# ubiquitel.net
KiCad netlist of a schematic drawn in EAGLE
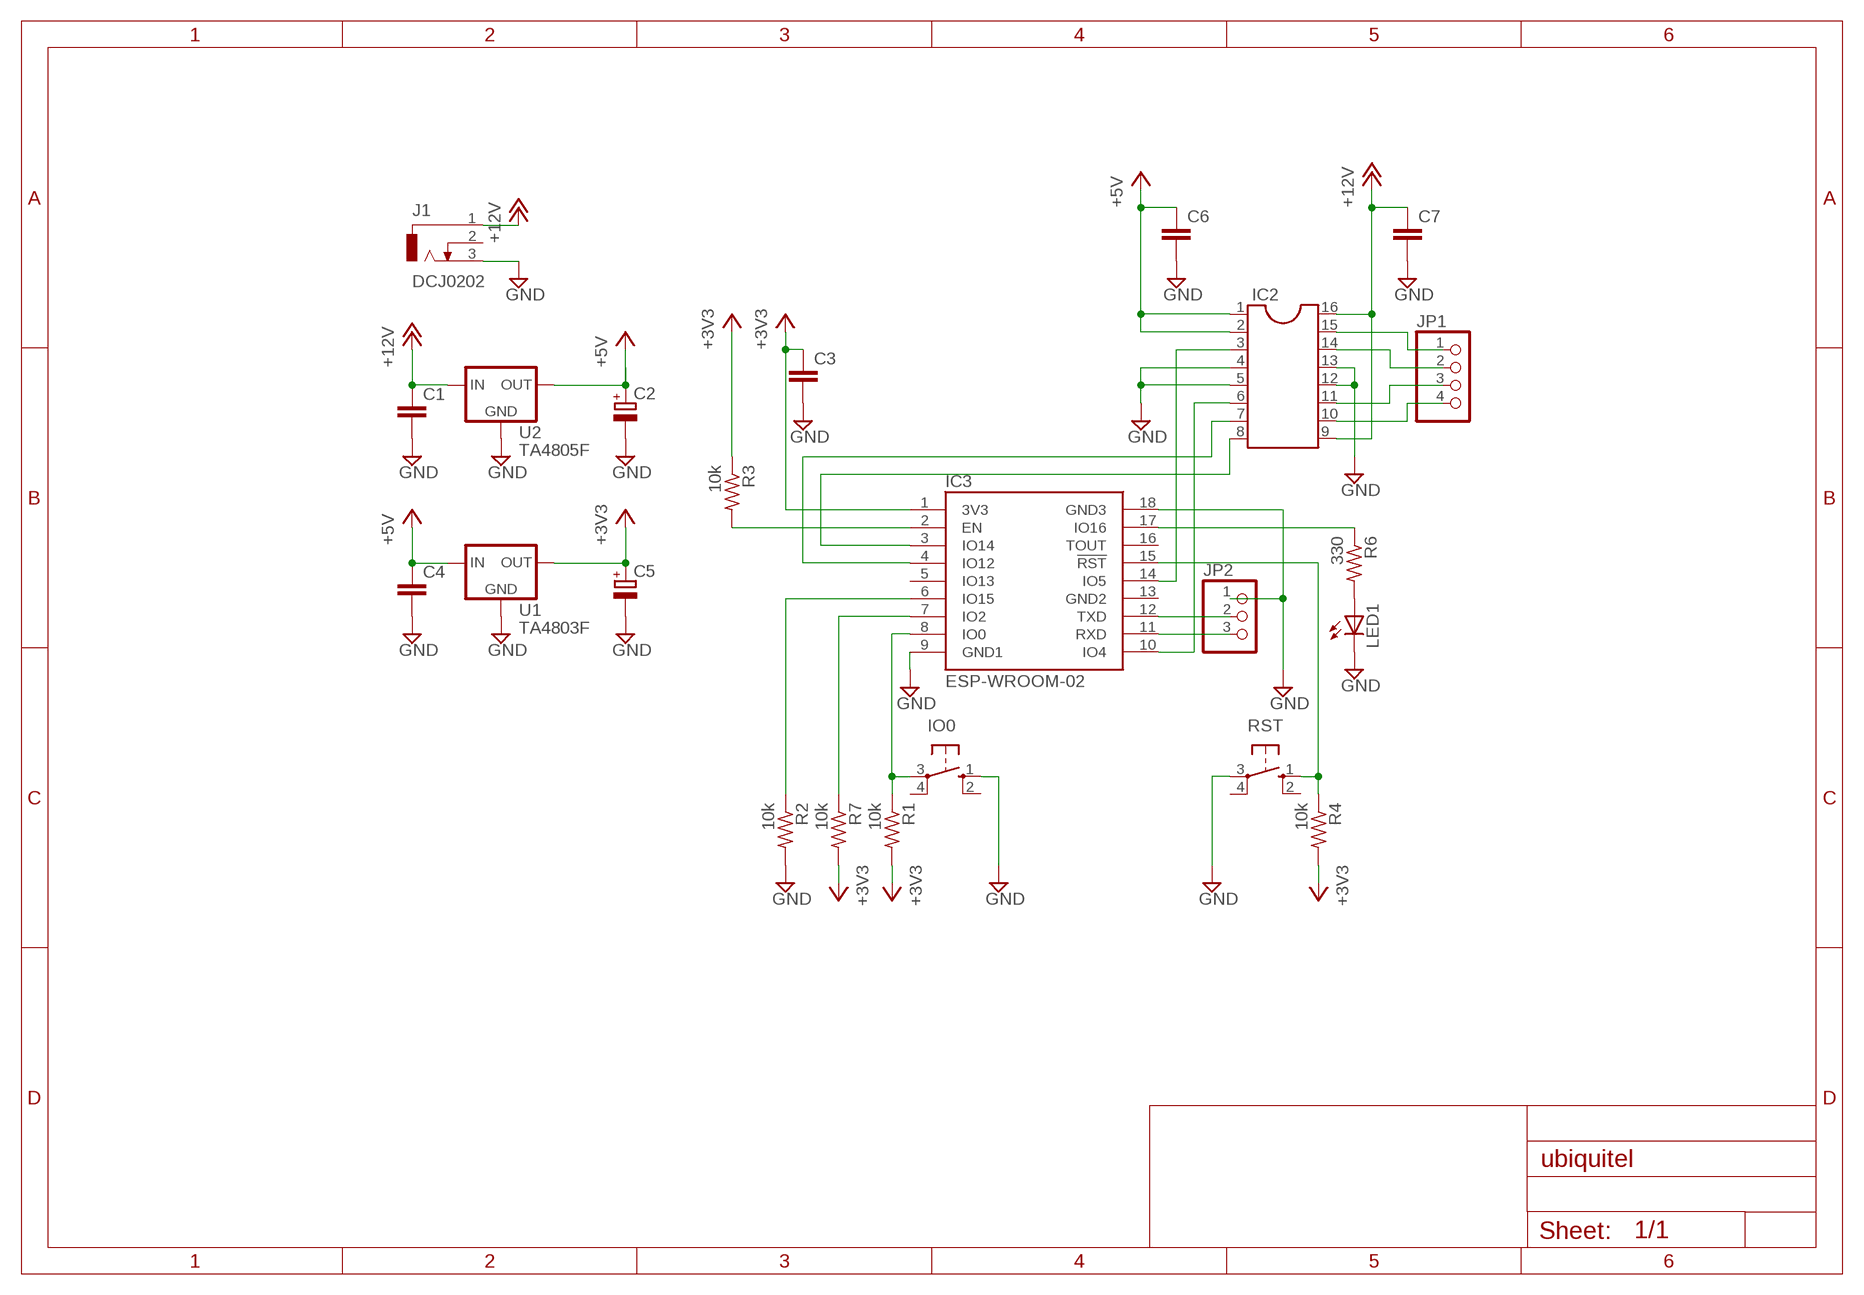
[diagram p0: schematic, sheet 1]

(export (version "E")
  (design (tool "Eeschema 10.0.6"))
  (components
    (comp (ref "C1")
      (value "C-EU025-024X044")
      (footprint "eagle-import:C025-024X044")
      (libsource (lib "eagle-import") (part "C-EU025-024X044"))
    )
    (comp (ref "C2")
      (value "CPOL-EUE2-5")
      (footprint "eagle-import:E2-5")
      (libsource (lib "eagle-import") (part "CPOL-EUE2-5"))
    )
    (comp (ref "C3")
      (value "C-EU025-024X044")
      (footprint "eagle-import:C025-024X044")
      (libsource (lib "eagle-import") (part "C-EU025-024X044"))
    )
    (comp (ref "C4")
      (value "C-EU025-024X044")
      (footprint "eagle-import:C025-024X044")
      (libsource (lib "eagle-import") (part "C-EU025-024X044"))
    )
    (comp (ref "C5")
      (value "CPOL-EUE2-5")
      (footprint "eagle-import:E2-5")
      (libsource (lib "eagle-import") (part "CPOL-EUE2-5"))
    )
    (comp (ref "C6")
      (value "C-EU025-024X044")
      (footprint "eagle-import:C025-024X044")
      (libsource (lib "eagle-import") (part "C-EU025-024X044"))
    )
    (comp (ref "C7")
      (value "C-EU025-024X044")
      (footprint "eagle-import:C025-024X044")
      (libsource (lib "eagle-import") (part "C-EU025-024X044"))
    )
    (comp (ref "IC2")
      (value "DIL16S")
      (footprint "eagle-import:SOCKET-16")
      (libsource (lib "eagle-import") (part "DIL16S"))
    )
    (comp (ref "IC3")
      (value "ESP-WROOM-02")
      (footprint "eagle-import:WROOM-02")
      (libsource (lib "eagle-import") (part "ESP-WROOM-02"))
    )
    (comp (ref "IO0")
      (value "10-XX(タクトスイッチ)")
      (footprint "eagle-import:B3F-10XX")
      (fields (field (name "MPN") "B3F-1000"))
      (libsource (lib "eagle-import") (part "10-XX(タクトスイッチ)"))
    )
    (comp (ref "J1")
      (value "DCJ0202")
      (footprint "eagle-import:DCJ0202")
      (libsource (lib "eagle-import") (part "DCJ0202"))
    )
    (comp (ref "JP1")
      (value "PINHD-1X4")
      (footprint "eagle-import:1X04")
      (libsource (lib "eagle-import") (part "PINHD-1X4"))
    )
    (comp (ref "JP2")
      (value "PINHD-1X3")
      (footprint "eagle-import:1X03")
      (libsource (lib "eagle-import") (part "PINHD-1X3"))
    )
    (comp (ref "LED1")
      (value "LED3MM")
      (footprint "eagle-import:LED3MM")
      (libsource (lib "eagle-import") (part "LED3MM"))
    )
    (comp (ref "R1")
      (value "10k")
      (footprint "eagle-import:0207_10")
      (libsource (lib "eagle-import") (part "R-US_0207/10"))
    )
    (comp (ref "R2")
      (value "10k")
      (footprint "eagle-import:0207_10")
      (libsource (lib "eagle-import") (part "R-US_0207/10"))
    )
    (comp (ref "R3")
      (value "10k")
      (footprint "eagle-import:0207_10")
      (libsource (lib "eagle-import") (part "R-US_0207/10"))
    )
    (comp (ref "R4")
      (value "10k")
      (footprint "eagle-import:0207_10")
      (libsource (lib "eagle-import") (part "R-US_0207/10"))
    )
    (comp (ref "R6")
      (value "330")
      (footprint "eagle-import:0207_10")
      (libsource (lib "eagle-import") (part "R-US_0207/10"))
    )
    (comp (ref "R7")
      (value "10k")
      (footprint "eagle-import:0207_10")
      (libsource (lib "eagle-import") (part "R-US_0207/10"))
    )
    (comp (ref "RST")
      (value "10-XX(タクトスイッチ)")
      (footprint "eagle-import:B3F-10XX")
      (fields (field (name "MPN") "B3F-1000"))
      (libsource (lib "eagle-import") (part "10-XX(タクトスイッチ)"))
    )
    (comp (ref "U1")
      (value "TA4803F")
      (footprint "eagle-import:CUSTOM")
      (libsource (lib "eagle-import") (part "TA48?03F"))
    )
    (comp (ref "U2")
      (value "TA4805F")
      (footprint "eagle-import:CUSTOM")
      (libsource (lib "eagle-import") (part "TA48?05F"))
    )
  )
  (nets
    (net (code "1") (name "+3V3") (class "Default")
      (node (ref "C3") (pin "1") (pinfunction "1_1") (pintype "passive"))
      (node (ref "C5") (pin "+") (pinfunction "+_+") (pintype "passive"))
      (node (ref "IC3") (pin "1") (pinfunction "3V3_1") (pintype "power_in"))
      (node (ref "R1") (pin "2") (pinfunction "2_2") (pintype "passive"))
      (node (ref "R3") (pin "1") (pinfunction "1_1") (pintype "passive"))
      (node (ref "R4") (pin "2") (pinfunction "2_2") (pintype "passive"))
      (node (ref "R7") (pin "2") (pinfunction "2_2") (pintype "passive"))
      (node (ref "U1") (pin "P$3") (pinfunction "OUT_P$3") (pintype "passive"))
    )
    (net (code "2") (name "+5V") (class "Default")
      (node (ref "C2") (pin "+") (pinfunction "+_+") (pintype "passive"))
      (node (ref "C4") (pin "1") (pinfunction "1_1") (pintype "passive"))
      (node (ref "C6") (pin "1") (pinfunction "1_1") (pintype "passive"))
      (node (ref "IC2") (pin "1") (pinfunction "1_1") (pintype "passive"))
      (node (ref "IC2") (pin "2") (pinfunction "2_2") (pintype "passive"))
      (node (ref "U1") (pin "P$1") (pinfunction "IN_P$1") (pintype "input"))
      (node (ref "U2") (pin "P$3") (pinfunction "OUT_P$3") (pintype "passive"))
    )
    (net (code "3") (name "+12V") (class "Default")
      (node (ref "C1") (pin "1") (pinfunction "1_1") (pintype "passive"))
      (node (ref "C7") (pin "1") (pinfunction "1_1") (pintype "passive"))
      (node (ref "IC2") (pin "16") (pinfunction "16_16") (pintype "passive"))
      (node (ref "IC2") (pin "9") (pinfunction "9_9") (pintype "passive"))
      (node (ref "J1") (pin "1") (pinfunction "1_1") (pintype "passive"))
      (node (ref "U2") (pin "P$1") (pinfunction "IN_P$1") (pintype "input"))
    )
    (net (code "4") (name "/GND2") (class "Default")
      (node (ref "IC3") (pin "13") (pinfunction "GND2_13") (pintype "power_in"))
    )
    (net (code "5") (name "GND") (class "Default")
      (node (ref "C1") (pin "2") (pinfunction "2_2") (pintype "passive"))
      (node (ref "C2") (pin "-") (pinfunction "-_-") (pintype "passive"))
      (node (ref "C3") (pin "2") (pinfunction "2_2") (pintype "passive"))
      (node (ref "C4") (pin "2") (pinfunction "2_2") (pintype "passive"))
      (node (ref "C5") (pin "-") (pinfunction "-_-") (pintype "passive"))
      (node (ref "C6") (pin "2") (pinfunction "2_2") (pintype "passive"))
      (node (ref "C7") (pin "2") (pinfunction "2_2") (pintype "passive"))
      (node (ref "IC2") (pin "12") (pinfunction "12_12") (pintype "passive"))
      (node (ref "IC2") (pin "13") (pinfunction "13_13") (pintype "passive"))
      (node (ref "IC2") (pin "4") (pinfunction "4_4") (pintype "passive"))
      (node (ref "IC2") (pin "5") (pinfunction "5_5") (pintype "passive"))
      (node (ref "IC3") (pin "18") (pinfunction "GND3_18") (pintype "power_in"))
      (node (ref "IC3") (pin "9") (pinfunction "GND1_9") (pintype "power_in"))
      (node (ref "IO0") (pin "1") (pinfunction "S_1") (pintype "passive"))
      (node (ref "J1") (pin "3") (pinfunction "3_3") (pintype "passive"))
      (node (ref "JP2") (pin "1") (pinfunction "1_1") (pintype "passive"))
      (node (ref "LED1") (pin "K") (pinfunction "C_K") (pintype "passive"))
      (node (ref "R2") (pin "2") (pinfunction "2_2") (pintype "passive"))
      (node (ref "RST") (pin "3") (pinfunction "P_3") (pintype "passive"))
      (node (ref "U1") (pin "P$2") (pinfunction "GND_P$2") (pintype "power_in"))
      (node (ref "U2") (pin "P$2") (pinfunction "GND_P$2") (pintype "power_in"))
    )
    (net (code "6") (name "Net-(IC2-Pad10)") (class "Default")
      (node (ref "IC2") (pin "10") (pinfunction "10_10") (pintype "passive"))
      (node (ref "JP1") (pin "4") (pinfunction "4_4") (pintype "passive"))
    )
    (net (code "7") (name "Net-(IC2-Pad11)") (class "Default")
      (node (ref "IC2") (pin "11") (pinfunction "11_11") (pintype "passive"))
      (node (ref "JP1") (pin "3") (pinfunction "3_3") (pintype "passive"))
    )
    (net (code "8") (name "Net-(IC2-Pad14)") (class "Default")
      (node (ref "IC2") (pin "14") (pinfunction "14_14") (pintype "passive"))
      (node (ref "JP1") (pin "2") (pinfunction "2_2") (pintype "passive"))
    )
    (net (code "9") (name "Net-(IC2-Pad15)") (class "Default")
      (node (ref "IC2") (pin "15") (pinfunction "15_15") (pintype "passive"))
      (node (ref "JP1") (pin "1") (pinfunction "1_1") (pintype "passive"))
    )
    (net (code "10") (name "Net-(IC3-EN)") (class "Default")
      (node (ref "IC3") (pin "2") (pinfunction "EN_2") (pintype "input"))
      (node (ref "R3") (pin "2") (pinfunction "2_2") (pintype "passive"))
    )
    (net (code "11") (name "Net-(IC3-IO0)") (class "Default")
      (node (ref "IC3") (pin "8") (pinfunction "IO0_8") (pintype "bidirectional"))
      (node (ref "IO0") (pin "3") (pinfunction "P_3") (pintype "passive"))
      (node (ref "R1") (pin "1") (pinfunction "1_1") (pintype "passive"))
    )
    (net (code "12") (name "Net-(IC3-IO2)") (class "Default")
      (node (ref "IC3") (pin "7") (pinfunction "IO2_7") (pintype "bidirectional"))
      (node (ref "R7") (pin "1") (pinfunction "1_1") (pintype "passive"))
    )
    (net (code "13") (name "Net-(IC3-IO4)") (class "Default")
      (node (ref "IC2") (pin "6") (pinfunction "6_6") (pintype "passive"))
      (node (ref "IC3") (pin "10") (pinfunction "IO4_10") (pintype "bidirectional"))
    )
    (net (code "14") (name "Net-(IC3-IO5)") (class "Default")
      (node (ref "IC2") (pin "3") (pinfunction "3_3") (pintype "passive"))
      (node (ref "IC3") (pin "14") (pinfunction "IO5_14") (pintype "bidirectional"))
    )
    (net (code "15") (name "Net-(IC3-IO12)") (class "Default")
      (node (ref "IC2") (pin "7") (pinfunction "7_7") (pintype "passive"))
      (node (ref "IC3") (pin "4") (pinfunction "IO12_4") (pintype "bidirectional"))
    )
    (net (code "16") (name "Net-(IC3-IO14)") (class "Default")
      (node (ref "IC2") (pin "8") (pinfunction "8_8") (pintype "passive"))
      (node (ref "IC3") (pin "3") (pinfunction "IO14_3") (pintype "bidirectional"))
    )
    (net (code "17") (name "Net-(IC3-IO15)") (class "Default")
      (node (ref "IC3") (pin "6") (pinfunction "IO15_6") (pintype "bidirectional"))
      (node (ref "R2") (pin "1") (pinfunction "1_1") (pintype "passive"))
    )
    (net (code "18") (name "Net-(IC3-IO16)") (class "Default")
      (node (ref "IC3") (pin "17") (pinfunction "IO16_17") (pintype "bidirectional"))
      (node (ref "R6") (pin "1") (pinfunction "1_1") (pintype "passive"))
    )
    (net (code "19") (name "Net-(IC3-RXD)") (class "Default")
      (node (ref "IC3") (pin "11") (pinfunction "RXD_11") (pintype "bidirectional"))
      (node (ref "JP2") (pin "3") (pinfunction "3_3") (pintype "passive"))
    )
    (net (code "20") (name "Net-(IC3-TXD)") (class "Default")
      (node (ref "IC3") (pin "12") (pinfunction "TXD_12") (pintype "bidirectional"))
      (node (ref "JP2") (pin "2") (pinfunction "2_2") (pintype "passive"))
    )
    (net (code "21") (name "Net-(IC3-~{RST})") (class "Default")
      (node (ref "IC3") (pin "15") (pinfunction "~{RST}_15") (pintype "input"))
      (node (ref "R4") (pin "1") (pinfunction "1_1") (pintype "passive"))
      (node (ref "RST") (pin "1") (pinfunction "S_1") (pintype "passive"))
    )
    (net (code "22") (name "Net-(LED1-PadA)") (class "Default")
      (node (ref "LED1") (pin "A") (pinfunction "A_A") (pintype "passive"))
      (node (ref "R6") (pin "2") (pinfunction "2_2") (pintype "passive"))
    )
    (net (code "23") (name "unconnected-(IC3-IO13-Pad5)") (class "Default")
      (node (ref "IC3") (pin "5") (pinfunction "IO13_5") (pintype "bidirectional"))
    )
    (net (code "24") (name "unconnected-(IC3-TOUT-Pad16)") (class "Default")
      (node (ref "IC3") (pin "16") (pinfunction "TOUT_16") (pintype "bidirectional"))
    )
    (net (code "25") (name "unconnected-(IO0-P1-Pad4)") (class "Default")
      (node (ref "IO0") (pin "4") (pinfunction "P1_4") (pintype "passive"))
    )
    (net (code "26") (name "unconnected-(IO0-S1-Pad2)") (class "Default")
      (node (ref "IO0") (pin "2") (pinfunction "S1_2") (pintype "passive"))
    )
    (net (code "27") (name "unconnected-(J1-Pad2)") (class "Default")
      (node (ref "J1") (pin "2") (pinfunction "2_2") (pintype "passive"))
    )
    (net (code "28") (name "unconnected-(RST-P1-Pad4)") (class "Default")
      (node (ref "RST") (pin "4") (pinfunction "P1_4") (pintype "passive"))
    )
    (net (code "29") (name "unconnected-(RST-S1-Pad2)") (class "Default")
      (node (ref "RST") (pin "2") (pinfunction "S1_2") (pintype "passive"))
    )
  )
)
